# zhuzhuan1.net
KiCad netlist of a schematic drawn in Altium Designer
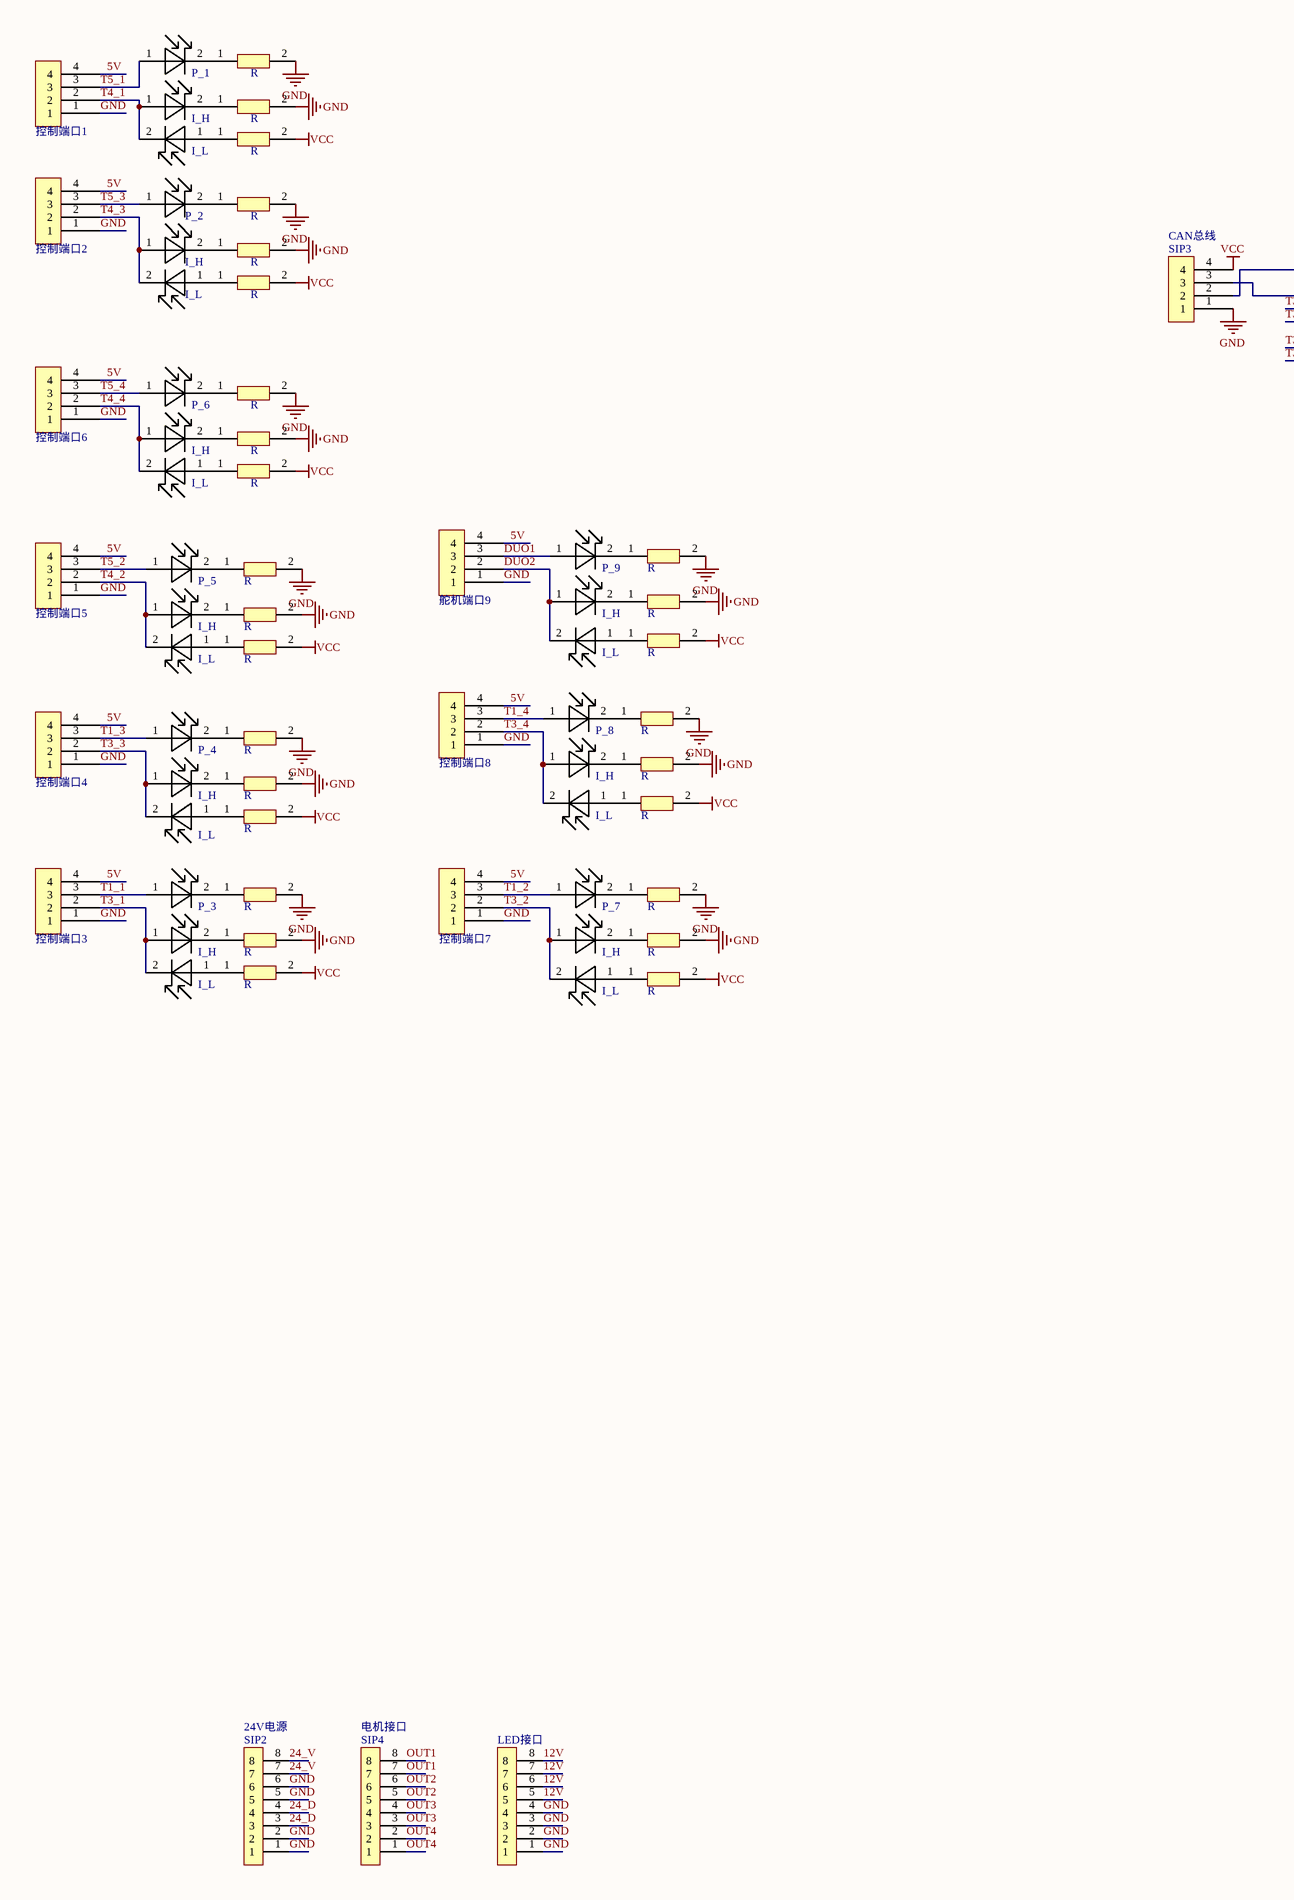
[diagram p0: zhuzhuan1.SchDoc, left]
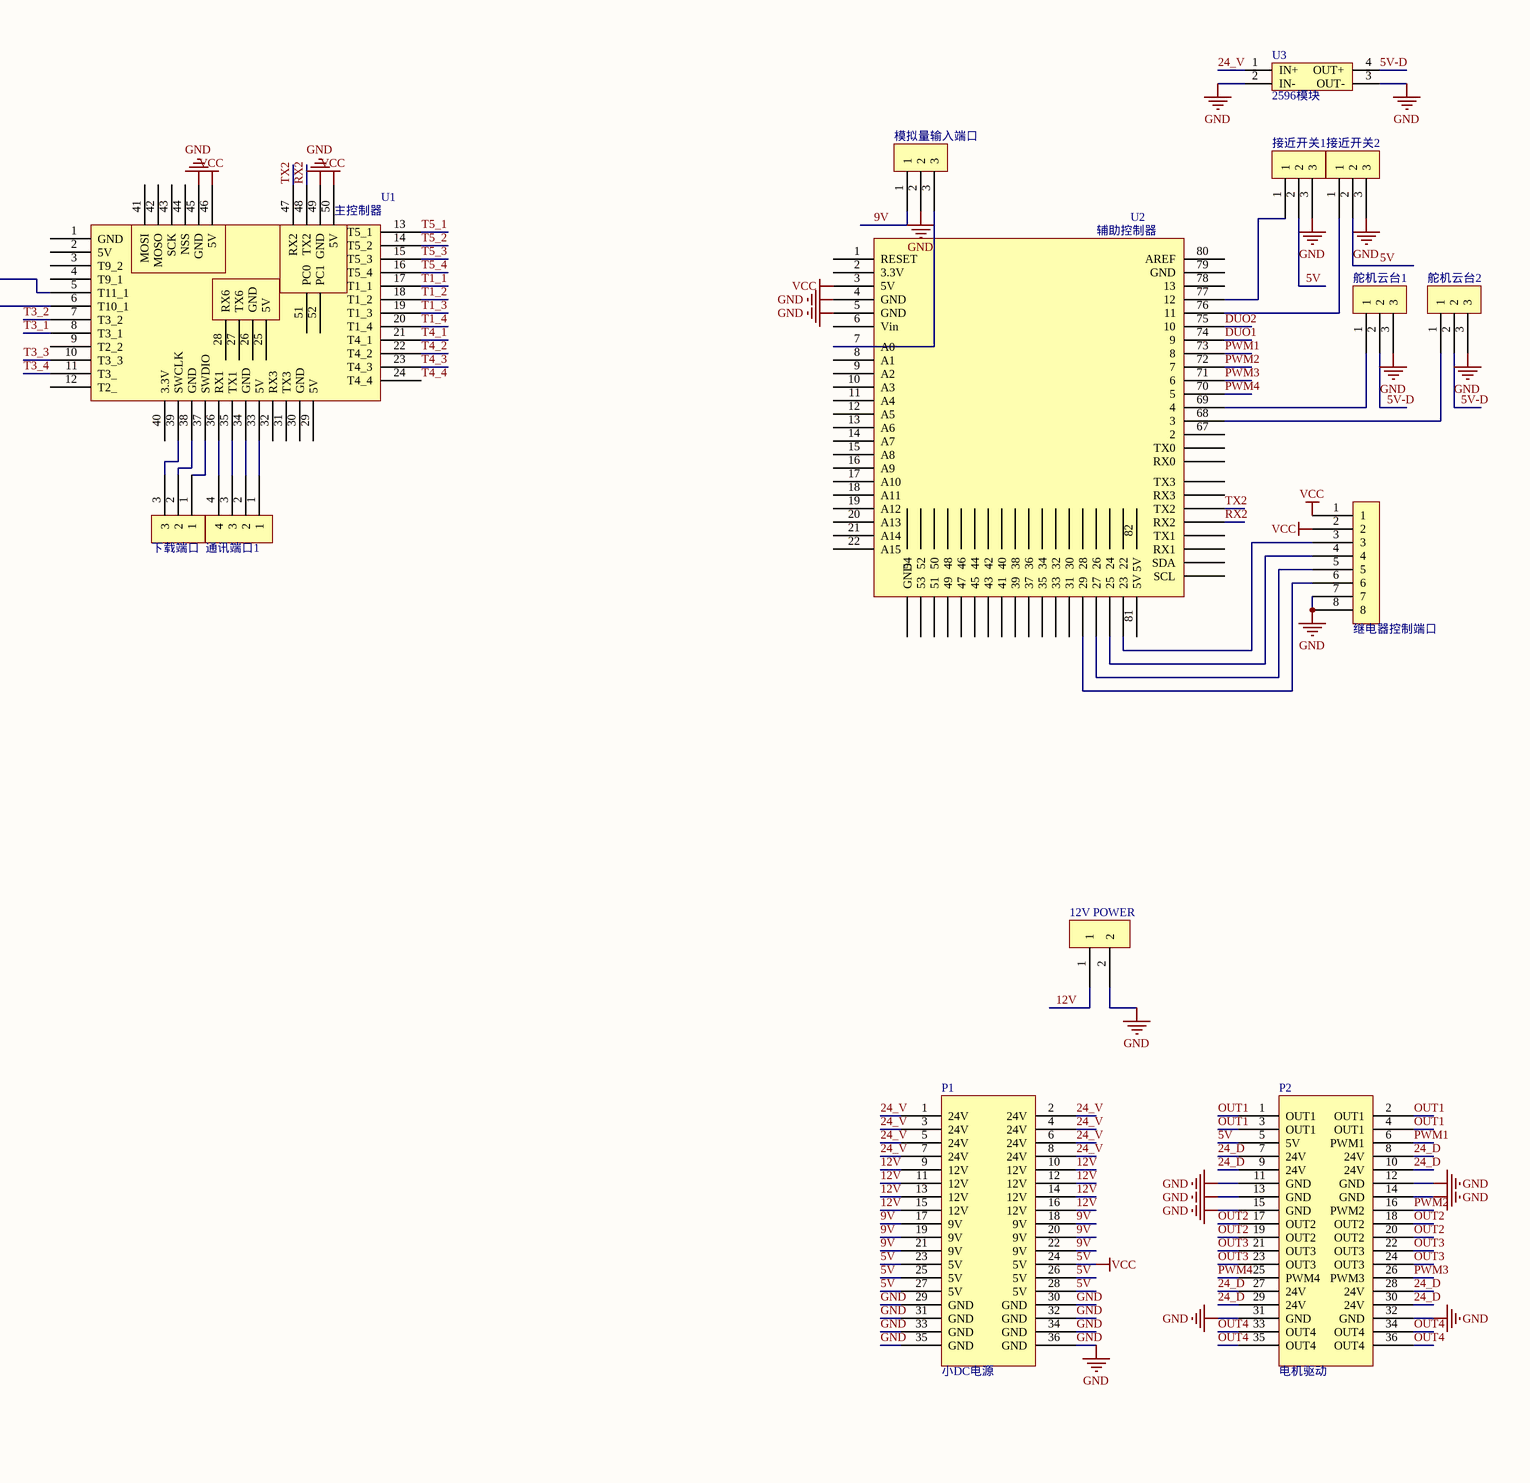
[diagram p1: zhuzhuan1.SchDoc, right]

(export (version "E")
  (design (tool "Eeschema 10.0.6"))
  (components
    (comp (ref "12V POWER") (value "SIP2") (footprint "SIP2-3MM") (libsource (lib "qudong") (part "SIP2")))
    (comp (ref "L1") (value "P_1") (footprint "LED-T") (libsource (lib "qudong") (part "LED")))
    (comp (ref "L2") (value "I_H") (footprint "LED-T") (libsource (lib "qudong") (part "LED")))
    (comp (ref "L3") (value "I_L") (footprint "LED-T") (libsource (lib "qudong") (part "LED")))
    (comp (ref "L4") (value "P_2") (footprint "LED-T") (libsource (lib "qudong") (part "LED")))
    (comp (ref "L5") (value "I_H") (footprint "LED-T") (libsource (lib "qudong") (part "LED")))
    (comp (ref "L6") (value "I_L") (footprint "LED-T") (libsource (lib "qudong") (part "LED")))
    (comp (ref "L7") (value "P_3") (footprint "LED-T") (libsource (lib "qudong") (part "LED")))
    (comp (ref "L8") (value "I_H") (footprint "LED-T") (libsource (lib "qudong") (part "LED")))
    (comp (ref "L9") (value "I_L") (footprint "LED-T") (libsource (lib "qudong") (part "LED")))
    (comp (ref "L10") (value "P_4") (footprint "LED-T") (libsource (lib "qudong") (part "LED")))
    (comp (ref "L11") (value "I_H") (footprint "LED-T") (libsource (lib "qudong") (part "LED")))
    (comp (ref "L12") (value "I_L") (footprint "LED-T") (libsource (lib "qudong") (part "LED")))
    (comp (ref "L13") (value "P_5") (footprint "LED-T") (libsource (lib "qudong") (part "LED")))
    (comp (ref "L14") (value "I_H") (footprint "LED-T") (libsource (lib "qudong") (part "LED")))
    (comp (ref "L15") (value "I_L") (footprint "LED-T") (libsource (lib "qudong") (part "LED")))
    (comp (ref "L16") (value "P_6") (footprint "LED-T") (libsource (lib "qudong") (part "LED")))
    (comp (ref "L17") (value "I_H") (footprint "LED-T") (libsource (lib "qudong") (part "LED")))
    (comp (ref "L18") (value "I_L") (footprint "LED-T") (libsource (lib "qudong") (part "LED")))
    (comp (ref "L19") (value "P_7") (footprint "LED-T") (libsource (lib "qudong") (part "LED")))
    (comp (ref "L20") (value "I_H") (footprint "LED-T") (libsource (lib "qudong") (part "LED")))
    (comp (ref "L21") (value "I_L") (footprint "LED-T") (libsource (lib "qudong") (part "LED")))
    (comp (ref "L22") (value "P_8") (footprint "LED-T") (libsource (lib "qudong") (part "LED")))
    (comp (ref "L23") (value "I_H") (footprint "LED-T") (libsource (lib "qudong") (part "LED")))
    (comp (ref "L24") (value "I_L") (footprint "LED-T") (libsource (lib "qudong") (part "LED")))
    (comp (ref "L25") (value "P_9") (footprint "LED-T") (libsource (lib "qudong") (part "LED")))
    (comp (ref "L26") (value "I_H") (footprint "LED-T") (libsource (lib "qudong") (part "LED")))
    (comp (ref "L27") (value "I_L") (footprint "LED-T") (libsource (lib "qudong") (part "LED")))
    (comp (ref "P1")
      (value "小DC电源")
      (footprint "DIP36-3.96MM")
      (libsource (lib "qudong") (part "POWER_18*2"))
    )
    (comp (ref "P2") (value "电机驱动") (footprint "DIP36-3.96MM") (libsource (lib "qudong") (part "Header")))
    (comp (ref "R1") (value "R") (footprint "RES-T") (libsource (lib "qudong") (part "RES-T")))
    (comp (ref "R2") (value "R") (footprint "RES-T") (libsource (lib "qudong") (part "RES-T")))
    (comp (ref "R3") (value "R") (footprint "RES-T") (libsource (lib "qudong") (part "RES-T")))
    (comp (ref "R4") (value "R") (footprint "RES-T") (libsource (lib "qudong") (part "RES-T")))
    (comp (ref "R5") (value "R") (footprint "RES-T") (libsource (lib "qudong") (part "RES-T")))
    (comp (ref "R6") (value "R") (footprint "RES-T") (libsource (lib "qudong") (part "RES-T")))
    (comp (ref "R7") (value "R") (footprint "RES-T") (libsource (lib "qudong") (part "RES-T")))
    (comp (ref "R8") (value "R") (footprint "RES-T") (libsource (lib "qudong") (part "RES-T")))
    (comp (ref "R9") (value "R") (footprint "RES-T") (libsource (lib "qudong") (part "RES-T")))
    (comp (ref "R10") (value "R") (footprint "RES-T") (libsource (lib "qudong") (part "RES-T")))
    (comp (ref "R11") (value "R") (footprint "RES-T") (libsource (lib "qudong") (part "RES-T")))
    (comp (ref "R12") (value "R") (footprint "RES-T") (libsource (lib "qudong") (part "RES-T")))
    (comp (ref "R13") (value "R") (footprint "RES-T") (libsource (lib "qudong") (part "RES-T")))
    (comp (ref "R14") (value "R") (footprint "RES-T") (libsource (lib "qudong") (part "RES-T")))
    (comp (ref "R15") (value "R") (footprint "RES-T") (libsource (lib "qudong") (part "RES-T")))
    (comp (ref "R16") (value "R") (footprint "RES-T") (libsource (lib "qudong") (part "RES-T")))
    (comp (ref "R17") (value "R") (footprint "RES-T") (libsource (lib "qudong") (part "RES-T")))
    (comp (ref "R18") (value "R") (footprint "RES-T") (libsource (lib "qudong") (part "RES-T")))
    (comp (ref "R19") (value "R") (footprint "RES-T") (libsource (lib "qudong") (part "RES-T")))
    (comp (ref "R20") (value "R") (footprint "RES-T") (libsource (lib "qudong") (part "RES-T")))
    (comp (ref "R21") (value "R") (footprint "RES-T") (libsource (lib "qudong") (part "RES-T")))
    (comp (ref "R22") (value "R") (footprint "RES-T") (libsource (lib "qudong") (part "RES-T")))
    (comp (ref "R23") (value "R") (footprint "RES-T") (libsource (lib "qudong") (part "RES-T")))
    (comp (ref "R24") (value "R") (footprint "RES-T") (libsource (lib "qudong") (part "RES-T")))
    (comp (ref "R25") (value "R") (footprint "RES-T") (libsource (lib "qudong") (part "RES-T")))
    (comp (ref "R26") (value "R") (footprint "RES-T") (libsource (lib "qudong") (part "RES-T")))
    (comp (ref "R27") (value "R") (footprint "RES-T") (libsource (lib "qudong") (part "RES-T")))
    (comp (ref "SIP2") (value "24V电源") (footprint "SIP8*3MM") (libsource (lib "qudong") (part "SIP8*3MM")))
    (comp (ref "SIP3") (value "CAN总线") (footprint "SIP4") (libsource (lib "qudong") (part "SIP4")))
    (comp (ref "SIP4") (value "电机接口") (footprint "SIP8*3MM") (libsource (lib "qudong") (part "SIP8*3MM")))
    (comp (ref "SIP5") (value "下载端口") (footprint "SIP3") (libsource (lib "") (part "SIP3_1")))
    (comp (ref "SIP7") (value "控制端口1") (footprint "SIP4") (libsource (lib "qudong") (part "SIP4")))
    (comp (ref "SIP8") (value "控制端口2") (footprint "SIP4") (libsource (lib "qudong") (part "SIP4")))
    (comp (ref "SIP9") (value "控制端口3") (footprint "SIP4") (libsource (lib "qudong") (part "SIP4")))
    (comp (ref "SIP10") (value "控制端口4") (footprint "SIP4") (libsource (lib "qudong") (part "SIP4")))
    (comp (ref "SIP11") (value "控制端口5") (footprint "SIP4") (libsource (lib "qudong") (part "SIP4")))
    (comp (ref "SIP12") (value "控制端口6") (footprint "SIP4") (libsource (lib "qudong") (part "SIP4")))
    (comp (ref "SIP13") (value "控制端口7") (footprint "SIP4") (libsource (lib "qudong") (part "SIP4")))
    (comp (ref "SIP14") (value "控制端口8") (footprint "SIP4") (libsource (lib "qudong") (part "SIP4")))
    (comp (ref "SIP15") (value "舵机云台1") (footprint "SIP3-3MM") (libsource (lib "qudong") (part "SIP3")))
    (comp (ref "SIP16") (value "舵机云台2") (footprint "SIP3-3MM") (libsource (lib "qudong") (part "SIP3")))
    (comp (ref "SIP17") (value "模拟量输入端口") (footprint "SIP3-3MM") (libsource (lib "qudong") (part "SIP3")))
    (comp (ref "SIP18") (value "舵机端口9") (footprint "SIP4") (libsource (lib "qudong") (part "SIP4")))
    (comp (ref "SIP19") (value "LED接口") (footprint "SIP8*3MM") (libsource (lib "qudong") (part "SIP8*3MM")))
    (comp (ref "SIP20") (value "接近开关1") (footprint "SIP3-3MM") (libsource (lib "qudong") (part "SIP3")))
    (comp (ref "SIP21") (value "接近开关2") (footprint "SIP3-3MM") (libsource (lib "qudong") (part "SIP3")))
    (comp (ref "SIP22") (value "继电器控制端口") (footprint "SIP8") (libsource (lib "qudong") (part "SIP8")))
    (comp (ref "U1")
      (value "主控制器")
      (footprint "-----STM32F407-----")
      (libsource (lib "qudong") (part "------STM32F407------"))
    )
    (comp (ref "U2")
      (value "辅助控制器")
      (footprint "ARDUINO 2560")
      (libsource (lib "qudong") (part "ARDUINO 2560"))
    )
    (comp (ref "U3") (value "2596模块") (footprint "2596模块") (libsource (lib "qudong") (part "2596模块")))
    (comp (ref "通讯端口1") (value "SIP4") (footprint "SIP4") (libsource (lib "") (part "SIP4_1")))
  )
  (nets
    (net (code "1") (name "/5V-D") (class "Default")
      (node (ref "SIP15") (pin "2") (pinfunction "2_2") (pintype "passive"))
      (node (ref "SIP16") (pin "2") (pinfunction "2_2") (pintype "passive"))
      (node (ref "U3") (pin "4") (pinfunction "OUT+_4") (pintype "passive"))
    )
    (net (code "2") (name "/9V") (class "Default")
      (node (ref "P1") (pin "17") (pinfunction "9V_17") (pintype "passive"))
      (node (ref "P1") (pin "18") (pinfunction "9V_18") (pintype "passive"))
      (node (ref "P1") (pin "19") (pinfunction "9V_19") (pintype "passive"))
      (node (ref "P1") (pin "20") (pinfunction "9V_20") (pintype "passive"))
      (node (ref "P1") (pin "21") (pinfunction "9V_21") (pintype "passive"))
      (node (ref "P1") (pin "22") (pinfunction "9V_22") (pintype "passive"))
      (node (ref "SIP17") (pin "1") (pinfunction "1_1") (pintype "passive"))
    )
    (net (code "3") (name "/12V") (class "Default")
      (node (ref "12V POWER") (pin "1") (pinfunction "1_1") (pintype "passive"))
      (node (ref "P1") (pin "10") (pinfunction "12V_10") (pintype "passive"))
      (node (ref "P1") (pin "11") (pinfunction "12V_11") (pintype "passive"))
      (node (ref "P1") (pin "12") (pinfunction "12V_12") (pintype "passive"))
      (node (ref "P1") (pin "13") (pinfunction "12V_13") (pintype "passive"))
      (node (ref "P1") (pin "14") (pinfunction "12V_14") (pintype "passive"))
      (node (ref "P1") (pin "15") (pinfunction "12V_15") (pintype "passive"))
      (node (ref "P1") (pin "16") (pinfunction "12V_16") (pintype "passive"))
      (node (ref "P1") (pin "9") (pinfunction "12V_9") (pintype "passive"))
      (node (ref "SIP19") (pin "5") (pinfunction "5_5") (pintype "passive"))
      (node (ref "SIP19") (pin "6") (pinfunction "6_6") (pintype "passive"))
      (node (ref "SIP19") (pin "7") (pinfunction "7_7") (pintype "passive"))
      (node (ref "SIP19") (pin "8") (pinfunction "8_8") (pintype "passive"))
    )
    (net (code "4") (name "/24_D") (class "Default")
      (node (ref "P2") (pin "10") (pinfunction "24V_10") (pintype "passive"))
      (node (ref "P2") (pin "27") (pinfunction "24V_27") (pintype "passive"))
      (node (ref "P2") (pin "28") (pinfunction "24V_28") (pintype "passive"))
      (node (ref "P2") (pin "29") (pinfunction "24V_29") (pintype "passive"))
      (node (ref "P2") (pin "30") (pinfunction "24V_30") (pintype "passive"))
      (node (ref "P2") (pin "7") (pinfunction "24V_7") (pintype "passive"))
      (node (ref "P2") (pin "8") (pinfunction "24V_8") (pintype "passive"))
      (node (ref "P2") (pin "9") (pinfunction "24V_9") (pintype "passive"))
      (node (ref "SIP2") (pin "3") (pinfunction "3_3") (pintype "passive"))
      (node (ref "SIP2") (pin "4") (pinfunction "4_4") (pintype "passive"))
    )
    (net (code "5") (name "/24_V") (class "Default")
      (node (ref "P1") (pin "1") (pinfunction "24V_1") (pintype "passive"))
      (node (ref "P1") (pin "2") (pinfunction "24V_2") (pintype "passive"))
      (node (ref "P1") (pin "3") (pinfunction "24V_3") (pintype "passive"))
      (node (ref "P1") (pin "4") (pinfunction "24V_4") (pintype "passive"))
      (node (ref "P1") (pin "5") (pinfunction "24V_5") (pintype "passive"))
      (node (ref "P1") (pin "6") (pinfunction "24V_6") (pintype "passive"))
      (node (ref "P1") (pin "7") (pinfunction "24V_7") (pintype "passive"))
      (node (ref "P1") (pin "8") (pinfunction "24V_8") (pintype "passive"))
      (node (ref "SIP2") (pin "7") (pinfunction "7_7") (pintype "passive"))
      (node (ref "SIP2") (pin "8") (pinfunction "8_8") (pintype "passive"))
      (node (ref "U3") (pin "1") (pinfunction "IN+_1") (pintype "passive"))
    )
    (net (code "6") (name "/DUO1") (class "Default")
      (node (ref "L25") (pin "1") (pinfunction "1_1") (pintype "passive"))
      (node (ref "SIP18") (pin "3") (pinfunction "3_3") (pintype "passive"))
      (node (ref "U2") (pin "74") (pinfunction "9_74") (pintype "passive"))
    )
    (net (code "7") (name "/DUO2") (class "Default")
      (node (ref "L26") (pin "1") (pinfunction "1_1") (pintype "passive"))
      (node (ref "L27") (pin "2") (pinfunction "2_2") (pintype "passive"))
      (node (ref "SIP18") (pin "2") (pinfunction "2_2") (pintype "passive"))
      (node (ref "U2") (pin "75") (pinfunction "10_75") (pintype "passive"))
    )
    (net (code "8") (name "/OUT1") (class "Default")
      (node (ref "P2") (pin "1") (pinfunction "OUT1_1") (pintype "passive"))
      (node (ref "P2") (pin "2") (pinfunction "OUT1_2") (pintype "passive"))
      (node (ref "P2") (pin "3") (pinfunction "OUT1_3") (pintype "passive"))
      (node (ref "P2") (pin "4") (pinfunction "OUT1_4") (pintype "passive"))
      (node (ref "SIP4") (pin "7") (pinfunction "7_7") (pintype "passive"))
      (node (ref "SIP4") (pin "8") (pinfunction "8_8") (pintype "passive"))
    )
    (net (code "9") (name "/OUT2") (class "Default")
      (node (ref "P2") (pin "17") (pinfunction "OUT2_17") (pintype "passive"))
      (node (ref "P2") (pin "18") (pinfunction "OUT2_18") (pintype "passive"))
      (node (ref "P2") (pin "19") (pinfunction "OUT2_19") (pintype "passive"))
      (node (ref "P2") (pin "20") (pinfunction "OUT2_20") (pintype "passive"))
      (node (ref "SIP4") (pin "5") (pinfunction "5_5") (pintype "passive"))
      (node (ref "SIP4") (pin "6") (pinfunction "6_6") (pintype "passive"))
    )
    (net (code "10") (name "/OUT3") (class "Default")
      (node (ref "P2") (pin "21") (pinfunction "OUT3_21") (pintype "passive"))
      (node (ref "P2") (pin "22") (pinfunction "OUT3_22") (pintype "passive"))
      (node (ref "P2") (pin "23") (pinfunction "OUT3_23") (pintype "passive"))
      (node (ref "P2") (pin "24") (pinfunction "OUT3_24") (pintype "passive"))
      (node (ref "SIP4") (pin "3") (pinfunction "3_3") (pintype "passive"))
      (node (ref "SIP4") (pin "4") (pinfunction "4_4") (pintype "passive"))
    )
    (net (code "11") (name "/OUT4") (class "Default")
      (node (ref "P2") (pin "33") (pinfunction "OUT4_33") (pintype "passive"))
      (node (ref "P2") (pin "34") (pinfunction "OUT4_34") (pintype "passive"))
      (node (ref "P2") (pin "35") (pinfunction "OUT4_35") (pintype "passive"))
      (node (ref "P2") (pin "36") (pinfunction "OUT4_36") (pintype "passive"))
      (node (ref "SIP4") (pin "1") (pinfunction "1_1") (pintype "passive"))
      (node (ref "SIP4") (pin "2") (pinfunction "2_2") (pintype "passive"))
    )
    (net (code "12") (name "/PWM1") (class "Default")
      (node (ref "P2") (pin "6") (pinfunction "PWM1_6") (pintype "passive"))
      (node (ref "U2") (pin "73") (pinfunction "8_73") (pintype "passive"))
    )
    (net (code "13") (name "/PWM2") (class "Default")
      (node (ref "P2") (pin "16") (pinfunction "PWM2_16") (pintype "passive"))
      (node (ref "U2") (pin "72") (pinfunction "7_72") (pintype "passive"))
    )
    (net (code "14") (name "/PWM3") (class "Default")
      (node (ref "P2") (pin "26") (pinfunction "PWM3_26") (pintype "passive"))
      (node (ref "U2") (pin "71") (pinfunction "6_71") (pintype "passive"))
    )
    (net (code "15") (name "/PWM4") (class "Default")
      (node (ref "P2") (pin "25") (pinfunction "PWM4_25") (pintype "passive"))
      (node (ref "U2") (pin "70") (pinfunction "5_70") (pintype "passive"))
    )
    (net (code "16") (name "/RX2") (class "Default")
      (node (ref "U1") (pin "48") (pinfunction "TX2_48") (pintype "passive"))
      (node (ref "U2") (pin "61") (pinfunction "RX2_61") (pintype "passive"))
    )
    (net (code "17") (name "/T1_1") (class "Default")
      (node (ref "L7") (pin "1") (pinfunction "1_1") (pintype "passive"))
      (node (ref "SIP9") (pin "3") (pinfunction "3_3") (pintype "passive"))
      (node (ref "U1") (pin "17") (pinfunction "T1_1_17") (pintype "passive"))
    )
    (net (code "18") (name "/T1_2") (class "Default")
      (node (ref "L19") (pin "1") (pinfunction "1_1") (pintype "passive"))
      (node (ref "SIP13") (pin "3") (pinfunction "3_3") (pintype "passive"))
      (node (ref "U1") (pin "18") (pinfunction "T1_2_18") (pintype "passive"))
    )
    (net (code "19") (name "/T1_3") (class "Default")
      (node (ref "L10") (pin "1") (pinfunction "1_1") (pintype "passive"))
      (node (ref "SIP10") (pin "3") (pinfunction "3_3") (pintype "passive"))
      (node (ref "U1") (pin "19") (pinfunction "T1_3_19") (pintype "passive"))
    )
    (net (code "20") (name "/T1_4") (class "Default")
      (node (ref "L22") (pin "1") (pinfunction "1_1") (pintype "passive"))
      (node (ref "SIP14") (pin "3") (pinfunction "3_3") (pintype "passive"))
      (node (ref "U1") (pin "20") (pinfunction "T1_4_20") (pintype "passive"))
    )
    (net (code "21") (name "/T3_1") (class "Default")
      (node (ref "L8") (pin "1") (pinfunction "1_1") (pintype "passive"))
      (node (ref "L9") (pin "2") (pinfunction "2_2") (pintype "passive"))
      (node (ref "SIP9") (pin "2") (pinfunction "2_2") (pintype "passive"))
      (node (ref "U1") (pin "8") (pinfunction "T3_1_8") (pintype "passive"))
    )
    (net (code "22") (name "/T3_2") (class "Default")
      (node (ref "L20") (pin "1") (pinfunction "1_1") (pintype "passive"))
      (node (ref "L21") (pin "2") (pinfunction "2_2") (pintype "passive"))
      (node (ref "SIP13") (pin "2") (pinfunction "2_2") (pintype "passive"))
      (node (ref "U1") (pin "7") (pinfunction "T3_2_7") (pintype "passive"))
    )
    (net (code "23") (name "/T3_3") (class "Default")
      (node (ref "L11") (pin "1") (pinfunction "1_1") (pintype "passive"))
      (node (ref "L12") (pin "2") (pinfunction "2_2") (pintype "passive"))
      (node (ref "SIP10") (pin "2") (pinfunction "2_2") (pintype "passive"))
      (node (ref "U1") (pin "10") (pinfunction "T3_3_10") (pintype "passive"))
    )
    (net (code "24") (name "/T3_4") (class "Default")
      (node (ref "L23") (pin "1") (pinfunction "1_1") (pintype "passive"))
      (node (ref "L24") (pin "2") (pinfunction "2_2") (pintype "passive"))
      (node (ref "SIP14") (pin "2") (pinfunction "2_2") (pintype "passive"))
      (node (ref "U1") (pin "11") (pinfunction "T3__11") (pintype "passive"))
    )
    (net (code "25") (name "/T4_1") (class "Default")
      (node (ref "L2") (pin "1") (pinfunction "1_1") (pintype "passive"))
      (node (ref "L3") (pin "2") (pinfunction "2_2") (pintype "passive"))
      (node (ref "SIP7") (pin "2") (pinfunction "2_2") (pintype "passive"))
      (node (ref "U1") (pin "21") (pinfunction "T4_1_21") (pintype "passive"))
    )
    (net (code "26") (name "/T4_2") (class "Default")
      (node (ref "L14") (pin "1") (pinfunction "1_1") (pintype "passive"))
      (node (ref "L15") (pin "2") (pinfunction "2_2") (pintype "passive"))
      (node (ref "SIP11") (pin "2") (pinfunction "2_2") (pintype "passive"))
      (node (ref "U1") (pin "22") (pinfunction "T4_2_22") (pintype "passive"))
    )
    (net (code "27") (name "/T4_3") (class "Default")
      (node (ref "L5") (pin "1") (pinfunction "1_1") (pintype "passive"))
      (node (ref "L6") (pin "2") (pinfunction "2_2") (pintype "passive"))
      (node (ref "SIP8") (pin "2") (pinfunction "2_2") (pintype "passive"))
      (node (ref "U1") (pin "23") (pinfunction "T4_3_23") (pintype "passive"))
    )
    (net (code "28") (name "/T4_4") (class "Default")
      (node (ref "L17") (pin "1") (pinfunction "1_1") (pintype "passive"))
      (node (ref "L18") (pin "2") (pinfunction "2_2") (pintype "passive"))
      (node (ref "SIP12") (pin "2") (pinfunction "2_2") (pintype "passive"))
      (node (ref "U1") (pin "24") (pinfunction "T4_4_24") (pintype "passive"))
    )
    (net (code "29") (name "/T5_1") (class "Default")
      (node (ref "L1") (pin "1") (pinfunction "1_1") (pintype "passive"))
      (node (ref "SIP7") (pin "3") (pinfunction "3_3") (pintype "passive"))
      (node (ref "U1") (pin "13") (pinfunction "T5_1_13") (pintype "passive"))
    )
    (net (code "30") (name "/T5_2") (class "Default")
      (node (ref "L13") (pin "1") (pinfunction "1_1") (pintype "passive"))
      (node (ref "SIP11") (pin "3") (pinfunction "3_3") (pintype "passive"))
      (node (ref "U1") (pin "14") (pinfunction "T5_2_14") (pintype "passive"))
    )
    (net (code "31") (name "/T5_3") (class "Default")
      (node (ref "L4") (pin "1") (pinfunction "1_1") (pintype "passive"))
      (node (ref "SIP8") (pin "3") (pinfunction "3_3") (pintype "passive"))
      (node (ref "U1") (pin "15") (pinfunction "T5_3_15") (pintype "passive"))
    )
    (net (code "32") (name "/T5_4") (class "Default")
      (node (ref "L16") (pin "1") (pinfunction "1_1") (pintype "passive"))
      (node (ref "SIP12") (pin "3") (pinfunction "3_3") (pintype "passive"))
      (node (ref "U1") (pin "16") (pinfunction "T5_4_16") (pintype "passive"))
    )
    (net (code "33") (name "/TX2") (class "Default")
      (node (ref "U1") (pin "47") (pinfunction "RX2_47") (pintype "passive"))
      (node (ref "U2") (pin "62") (pinfunction "TX2_62") (pintype "passive"))
    )
    (net (code "34") (name "GND") (class "Default")
      (node (ref "12V POWER") (pin "2") (pinfunction "2_2") (pintype "passive"))
      (node (ref "P1") (pin "29") (pinfunction "GND_29") (pintype "passive"))
      (node (ref "P1") (pin "30") (pinfunction "GND_30") (pintype "passive"))
      (node (ref "P1") (pin "31") (pinfunction "GND_31") (pintype "passive"))
      (node (ref "P1") (pin "32") (pinfunction "GND_32") (pintype "passive"))
      (node (ref "P1") (pin "33") (pinfunction "GND_33") (pintype "passive"))
      (node (ref "P1") (pin "34") (pinfunction "GND_34") (pintype "passive"))
      (node (ref "P1") (pin "35") (pinfunction "GND_35") (pintype "passive"))
      (node (ref "P1") (pin "36") (pinfunction "GND_36") (pintype "passive"))
      (node (ref "P2") (pin "11") (pinfunction "GND_11") (pintype "passive"))
      (node (ref "P2") (pin "12") (pinfunction "GND_12") (pintype "passive"))
      (node (ref "P2") (pin "13") (pinfunction "GND_13") (pintype "passive"))
      (node (ref "P2") (pin "14") (pinfunction "GND_14") (pintype "passive"))
      (node (ref "P2") (pin "15") (pinfunction "GND_15") (pintype "passive"))
      (node (ref "P2") (pin "31") (pinfunction "GND_31") (pintype "passive"))
      (node (ref "P2") (pin "32") (pinfunction "GND_32") (pintype "passive"))
      (node (ref "R1") (pin "2") (pinfunction "2_2") (pintype "passive"))
      (node (ref "R10") (pin "2") (pinfunction "2_2") (pintype "passive"))
      (node (ref "R11") (pin "2") (pinfunction "2_2") (pintype "passive"))
      (node (ref "R13") (pin "2") (pinfunction "2_2") (pintype "passive"))
      (node (ref "R14") (pin "2") (pinfunction "2_2") (pintype "passive"))
      (node (ref "R16") (pin "2") (pinfunction "2_2") (pintype "passive"))
      (node (ref "R17") (pin "2") (pinfunction "2_2") (pintype "passive"))
      (node (ref "R19") (pin "2") (pinfunction "2_2") (pintype "passive"))
      (node (ref "R2") (pin "2") (pinfunction "2_2") (pintype "passive"))
      (node (ref "R20") (pin "2") (pinfunction "2_2") (pintype "passive"))
      (node (ref "R22") (pin "2") (pinfunction "2_2") (pintype "passive"))
      (node (ref "R23") (pin "2") (pinfunction "2_2") (pintype "passive"))
      (node (ref "R25") (pin "2") (pinfunction "2_2") (pintype "passive"))
      (node (ref "R26") (pin "2") (pinfunction "2_2") (pintype "passive"))
      (node (ref "R4") (pin "2") (pinfunction "2_2") (pintype "passive"))
      (node (ref "R5") (pin "2") (pinfunction "2_2") (pintype "passive"))
      (node (ref "R7") (pin "2") (pinfunction "2_2") (pintype "passive"))
      (node (ref "R8") (pin "2") (pinfunction "2_2") (pintype "passive"))
      (node (ref "SIP10") (pin "1") (pinfunction "1_1") (pintype "passive"))
      (node (ref "SIP11") (pin "1") (pinfunction "1_1") (pintype "passive"))
      (node (ref "SIP12") (pin "1") (pinfunction "1_1") (pintype "passive"))
      (node (ref "SIP13") (pin "1") (pinfunction "1_1") (pintype "passive"))
      (node (ref "SIP14") (pin "1") (pinfunction "1_1") (pintype "passive"))
      (node (ref "SIP15") (pin "3") (pinfunction "3_3") (pintype "passive"))
      (node (ref "SIP16") (pin "3") (pinfunction "3_3") (pintype "passive"))
      (node (ref "SIP17") (pin "2") (pinfunction "2_2") (pintype "passive"))
      (node (ref "SIP18") (pin "1") (pinfunction "1_1") (pintype "passive"))
      (node (ref "SIP19") (pin "1") (pinfunction "1_1") (pintype "passive"))
      (node (ref "SIP19") (pin "2") (pinfunction "2_2") (pintype "passive"))
      (node (ref "SIP19") (pin "3") (pinfunction "3_3") (pintype "passive"))
      (node (ref "SIP19") (pin "4") (pinfunction "4_4") (pintype "passive"))
      (node (ref "SIP2") (pin "1") (pinfunction "1_1") (pintype "passive"))
      (node (ref "SIP2") (pin "2") (pinfunction "2_2") (pintype "passive"))
      (node (ref "SIP2") (pin "5") (pinfunction "5_5") (pintype "passive"))
      (node (ref "SIP2") (pin "6") (pinfunction "6_6") (pintype "passive"))
      (node (ref "SIP20") (pin "3") (pinfunction "3_3") (pintype "passive"))
      (node (ref "SIP21") (pin "3") (pinfunction "3_3") (pintype "passive"))
      (node (ref "SIP22") (pin "7") (pinfunction "7_7") (pintype "passive"))
      (node (ref "SIP22") (pin "8") (pinfunction "8_8") (pintype "passive"))
      (node (ref "SIP3") (pin "1") (pinfunction "1_1") (pintype "passive"))
      (node (ref "SIP7") (pin "1") (pinfunction "1_1") (pintype "passive"))
      (node (ref "SIP8") (pin "1") (pinfunction "1_1") (pintype "passive"))
      (node (ref "SIP9") (pin "1") (pinfunction "1_1") (pintype "passive"))
      (node (ref "U1") (pin "45") (pinfunction "GND_45") (pintype "passive"))
      (node (ref "U1") (pin "49") (pinfunction "GND_49") (pintype "passive"))
      (node (ref "U2") (pin "4") (pinfunction "GND_4") (pintype "passive"))
      (node (ref "U2") (pin "5") (pinfunction "GND_5") (pintype "passive"))
      (node (ref "U3") (pin "2") (pinfunction "IN-_2") (pintype "passive"))
      (node (ref "U3") (pin "3") (pinfunction "OUT-_3") (pintype "passive"))
    )
    (net (code "35") (name "Net-(L1-Pad2)") (class "Default")
      (node (ref "L1") (pin "2") (pinfunction "2_2") (pintype "passive"))
      (node (ref "R1") (pin "1") (pinfunction "1_1") (pintype "passive"))
    )
    (net (code "36") (name "Net-(L2-Pad2)") (class "Default")
      (node (ref "L2") (pin "2") (pinfunction "2_2") (pintype "passive"))
      (node (ref "R2") (pin "1") (pinfunction "1_1") (pintype "passive"))
    )
    (net (code "37") (name "Net-(L3-Pad1)") (class "Default")
      (node (ref "L3") (pin "1") (pinfunction "1_1") (pintype "passive"))
      (node (ref "R3") (pin "1") (pinfunction "1_1") (pintype "passive"))
    )
    (net (code "38") (name "Net-(L4-Pad2)") (class "Default")
      (node (ref "L4") (pin "2") (pinfunction "2_2") (pintype "passive"))
      (node (ref "R4") (pin "1") (pinfunction "1_1") (pintype "passive"))
    )
    (net (code "39") (name "Net-(L5-Pad2)") (class "Default")
      (node (ref "L5") (pin "2") (pinfunction "2_2") (pintype "passive"))
      (node (ref "R5") (pin "1") (pinfunction "1_1") (pintype "passive"))
    )
    (net (code "40") (name "Net-(L6-Pad1)") (class "Default")
      (node (ref "L6") (pin "1") (pinfunction "1_1") (pintype "passive"))
      (node (ref "R6") (pin "1") (pinfunction "1_1") (pintype "passive"))
    )
    (net (code "41") (name "Net-(L7-Pad2)") (class "Default")
      (node (ref "L7") (pin "2") (pinfunction "2_2") (pintype "passive"))
      (node (ref "R7") (pin "1") (pinfunction "1_1") (pintype "passive"))
    )
    (net (code "42") (name "Net-(L8-Pad2)") (class "Default")
      (node (ref "L8") (pin "2") (pinfunction "2_2") (pintype "passive"))
      (node (ref "R8") (pin "1") (pinfunction "1_1") (pintype "passive"))
    )
    (net (code "43") (name "Net-(L9-Pad1)") (class "Default")
      (node (ref "L9") (pin "1") (pinfunction "1_1") (pintype "passive"))
      (node (ref "R9") (pin "1") (pinfunction "1_1") (pintype "passive"))
    )
    (net (code "44") (name "Net-(L10-Pad2)") (class "Default")
      (node (ref "L10") (pin "2") (pinfunction "2_2") (pintype "passive"))
      (node (ref "R10") (pin "1") (pinfunction "1_1") (pintype "passive"))
    )
    (net (code "45") (name "Net-(L11-Pad2)") (class "Default")
      (node (ref "L11") (pin "2") (pinfunction "2_2") (pintype "passive"))
      (node (ref "R11") (pin "1") (pinfunction "1_1") (pintype "passive"))
    )
    (net (code "46") (name "Net-(L12-Pad1)") (class "Default")
      (node (ref "L12") (pin "1") (pinfunction "1_1") (pintype "passive"))
      (node (ref "R12") (pin "1") (pinfunction "1_1") (pintype "passive"))
    )
    (net (code "47") (name "Net-(L13-Pad2)") (class "Default")
      (node (ref "L13") (pin "2") (pinfunction "2_2") (pintype "passive"))
      (node (ref "R13") (pin "1") (pinfunction "1_1") (pintype "passive"))
    )
    (net (code "48") (name "Net-(L14-Pad2)") (class "Default")
      (node (ref "L14") (pin "2") (pinfunction "2_2") (pintype "passive"))
      (node (ref "R14") (pin "1") (pinfunction "1_1") (pintype "passive"))
    )
    (net (code "49") (name "Net-(L15-Pad1)") (class "Default")
      (node (ref "L15") (pin "1") (pinfunction "1_1") (pintype "passive"))
      (node (ref "R15") (pin "1") (pinfunction "1_1") (pintype "passive"))
    )
    (net (code "50") (name "Net-(L16-Pad2)") (class "Default")
      (node (ref "L16") (pin "2") (pinfunction "2_2") (pintype "passive"))
      (node (ref "R16") (pin "1") (pinfunction "1_1") (pintype "passive"))
    )
    (net (code "51") (name "Net-(L17-Pad2)") (class "Default")
      (node (ref "L17") (pin "2") (pinfunction "2_2") (pintype "passive"))
      (node (ref "R17") (pin "1") (pinfunction "1_1") (pintype "passive"))
    )
    (net (code "52") (name "Net-(L18-Pad1)") (class "Default")
      (node (ref "L18") (pin "1") (pinfunction "1_1") (pintype "passive"))
      (node (ref "R18") (pin "1") (pinfunction "1_1") (pintype "passive"))
    )
    (net (code "53") (name "Net-(L19-Pad2)") (class "Default")
      (node (ref "L19") (pin "2") (pinfunction "2_2") (pintype "passive"))
      (node (ref "R19") (pin "1") (pinfunction "1_1") (pintype "passive"))
    )
    (net (code "54") (name "Net-(L20-Pad2)") (class "Default")
      (node (ref "L20") (pin "2") (pinfunction "2_2") (pintype "passive"))
      (node (ref "R20") (pin "1") (pinfunction "1_1") (pintype "passive"))
    )
    (net (code "55") (name "Net-(L21-Pad1)") (class "Default")
      (node (ref "L21") (pin "1") (pinfunction "1_1") (pintype "passive"))
      (node (ref "R21") (pin "1") (pinfunction "1_1") (pintype "passive"))
    )
    (net (code "56") (name "Net-(L22-Pad2)") (class "Default")
      (node (ref "L22") (pin "2") (pinfunction "2_2") (pintype "passive"))
      (node (ref "R22") (pin "1") (pinfunction "1_1") (pintype "passive"))
    )
    (net (code "57") (name "Net-(L23-Pad2)") (class "Default")
      (node (ref "L23") (pin "2") (pinfunction "2_2") (pintype "passive"))
      (node (ref "R23") (pin "1") (pinfunction "1_1") (pintype "passive"))
    )
    (net (code "58") (name "Net-(L24-Pad1)") (class "Default")
      (node (ref "L24") (pin "1") (pinfunction "1_1") (pintype "passive"))
      (node (ref "R24") (pin "1") (pinfunction "1_1") (pintype "passive"))
    )
    (net (code "59") (name "Net-(L25-Pad2)") (class "Default")
      (node (ref "L25") (pin "2") (pinfunction "2_2") (pintype "passive"))
      (node (ref "R25") (pin "1") (pinfunction "1_1") (pintype "passive"))
    )
    (net (code "60") (name "Net-(L26-Pad2)") (class "Default")
      (node (ref "L26") (pin "2") (pinfunction "2_2") (pintype "passive"))
      (node (ref "R26") (pin "1") (pinfunction "1_1") (pintype "passive"))
    )
    (net (code "61") (name "Net-(L27-Pad1)") (class "Default")
      (node (ref "L27") (pin "1") (pinfunction "1_1") (pintype "passive"))
      (node (ref "R27") (pin "1") (pinfunction "1_1") (pintype "passive"))
    )
    (net (code "62") (name "Net-(SIP5-Pad2)") (class "Default")
      (node (ref "SIP5") (pin "2") (pinfunction "2_2") (pintype "passive"))
      (node (ref "U1") (pin "38") (pinfunction "GND_38") (pintype "passive"))
    )
    (net (code "63") (name "Net-(U1-5V-Pad33)") (class "Default")
      (node (ref "U1") (pin "33") (pinfunction "5V_33") (pintype "passive"))
      (node (ref "通讯端口1") (pin "1") (pinfunction "1_1") (pintype "passive"))
    )
    (net (code "64") (name "Net-(U1-GND-Pad34)") (class "Default")
      (node (ref "U1") (pin "34") (pinfunction "GND_34") (pintype "passive"))
      (node (ref "通讯端口1") (pin "2") (pinfunction "2_2") (pintype "passive"))
    )
    (net (code "65") (name "Net-(U1-RX1)") (class "Default")
      (node (ref "U1") (pin "36") (pinfunction "RX1_36") (pintype "passive"))
      (node (ref "通讯端口1") (pin "4") (pinfunction "4_4") (pintype "passive"))
    )
    (net (code "66") (name "Net-(U1-SWCLK)") (class "Default")
      (node (ref "SIP5") (pin "3") (pinfunction "3_3") (pintype "passive"))
      (node (ref "U1") (pin "39") (pinfunction "SWCLK_39") (pintype "passive"))
    )
    (net (code "67") (name "Net-(U1-SWDIO)") (class "Default")
      (node (ref "SIP5") (pin "1") (pinfunction "1_1") (pintype "passive"))
      (node (ref "U1") (pin "37") (pinfunction "SWDIO_37") (pintype "passive"))
    )
    (net (code "68") (name "Net-(U1-T10_1)") (class "Default")
      (node (ref "SIP3") (pin "3") (pinfunction "3_3") (pintype "passive"))
      (node (ref "U1") (pin "6") (pinfunction "T10_1_6") (pintype "passive"))
    )
    (net (code "69") (name "Net-(U1-T11_1)") (class "Default")
      (node (ref "SIP3") (pin "2") (pinfunction "2_2") (pintype "passive"))
      (node (ref "U1") (pin "5") (pinfunction "T11_1_5") (pintype "passive"))
    )
    (net (code "70") (name "Net-(U1-TX1)") (class "Default")
      (node (ref "U1") (pin "35") (pinfunction "TX1_35") (pintype "passive"))
      (node (ref "通讯端口1") (pin "3") (pinfunction "3_3") (pintype "passive"))
    )
    (net (code "71") (name "Net-(U2-3)") (class "Default")
      (node (ref "SIP16") (pin "1") (pinfunction "1_1") (pintype "passive"))
      (node (ref "U2") (pin "68") (pinfunction "3_68") (pintype "passive"))
    )
    (net (code "72") (name "Net-(U2-4)") (class "Default")
      (node (ref "SIP15") (pin "1") (pinfunction "1_1") (pintype "passive"))
      (node (ref "U2") (pin "69") (pinfunction "4_69") (pintype "passive"))
    )
    (net (code "73") (name "Net-(U2-11)") (class "Default")
      (node (ref "SIP21") (pin "1") (pinfunction "1_1") (pintype "passive"))
      (node (ref "U2") (pin "76") (pinfunction "11_76") (pintype "passive"))
    )
    (net (code "74") (name "Net-(U2-12)") (class "Default")
      (node (ref "SIP20") (pin "1") (pinfunction "1_1") (pintype "passive"))
      (node (ref "U2") (pin "77") (pinfunction "12_77") (pintype "passive"))
    )
    (net (code "75") (name "Net-(U2-23)") (class "Default")
      (node (ref "SIP22") (pin "3") (pinfunction "3_3") (pintype "passive"))
      (node (ref "U2") (pin "24") (pinfunction "23_24") (pintype "passive"))
    )
    (net (code "76") (name "Net-(U2-25)") (class "Default")
      (node (ref "SIP22") (pin "4") (pinfunction "4_4") (pintype "passive"))
      (node (ref "U2") (pin "26") (pinfunction "25_26") (pintype "passive"))
    )
    (net (code "77") (name "Net-(U2-27)") (class "Default")
      (node (ref "SIP22") (pin "5") (pinfunction "5_5") (pintype "passive"))
      (node (ref "U2") (pin "28") (pinfunction "27_28") (pintype "passive"))
    )
    (net (code "78") (name "Net-(U2-29)") (class "Default")
      (node (ref "SIP22") (pin "6") (pinfunction "6_6") (pintype "passive"))
      (node (ref "U2") (pin "30") (pinfunction "29_30") (pintype "passive"))
    )
    (net (code "79") (name "Net-(U2-A0)") (class "Default")
      (node (ref "SIP17") (pin "3") (pinfunction "3_3") (pintype "passive"))
      (node (ref "U2") (pin "7") (pinfunction "A0_7") (pintype "passive"))
    )
    (net (code "80") (name "VCC") (class "Default")
      (node (ref "P1") (pin "23") (pinfunction "5V_23") (pintype "passive"))
      (node (ref "P1") (pin "24") (pinfunction "5V_24") (pintype "passive"))
      (node (ref "P1") (pin "25") (pinfunction "5V_25") (pintype "passive"))
      (node (ref "P1") (pin "26") (pinfunction "5V_26") (pintype "passive"))
      (node (ref "P1") (pin "27") (pinfunction "5V_27") (pintype "passive"))
      (node (ref "P1") (pin "28") (pinfunction "5V_28") (pintype "passive"))
      (node (ref "P2") (pin "5") (pinfunction "5V_5") (pintype "passive"))
      (node (ref "R12") (pin "2") (pinfunction "2_2") (pintype "passive"))
      (node (ref "R15") (pin "2") (pinfunction "2_2") (pintype "passive"))
      (node (ref "R18") (pin "2") (pinfunction "2_2") (pintype "passive"))
      (node (ref "R21") (pin "2") (pinfunction "2_2") (pintype "passive"))
      (node (ref "R24") (pin "2") (pinfunction "2_2") (pintype "passive"))
      (node (ref "R27") (pin "2") (pinfunction "2_2") (pintype "passive"))
      (node (ref "R3") (pin "2") (pinfunction "2_2") (pintype "passive"))
      (node (ref "R6") (pin "2") (pinfunction "2_2") (pintype "passive"))
      (node (ref "R9") (pin "2") (pinfunction "2_2") (pintype "passive"))
      (node (ref "SIP10") (pin "4") (pinfunction "4_4") (pintype "passive"))
      (node (ref "SIP11") (pin "4") (pinfunction "4_4") (pintype "passive"))
      (node (ref "SIP12") (pin "4") (pinfunction "4_4") (pintype "passive"))
      (node (ref "SIP13") (pin "4") (pinfunction "4_4") (pintype "passive"))
      (node (ref "SIP14") (pin "4") (pinfunction "4_4") (pintype "passive"))
      (node (ref "SIP18") (pin "4") (pinfunction "4_4") (pintype "passive"))
      (node (ref "SIP20") (pin "2") (pinfunction "2_2") (pintype "passive"))
      (node (ref "SIP21") (pin "2") (pinfunction "2_2") (pintype "passive"))
      (node (ref "SIP22") (pin "1") (pinfunction "1_1") (pintype "passive"))
      (node (ref "SIP22") (pin "2") (pinfunction "2_2") (pintype "passive"))
      (node (ref "SIP3") (pin "4") (pinfunction "4_4") (pintype "passive"))
      (node (ref "SIP7") (pin "4") (pinfunction "4_4") (pintype "passive"))
      (node (ref "SIP8") (pin "4") (pinfunction "4_4") (pintype "passive"))
      (node (ref "SIP9") (pin "4") (pinfunction "4_4") (pintype "passive"))
      (node (ref "U1") (pin "46") (pinfunction "5V_46") (pintype "passive"))
      (node (ref "U1") (pin "50") (pinfunction "5V_50") (pintype "passive"))
      (node (ref "U2") (pin "3") (pinfunction "5V_3") (pintype "passive"))
    )
    (net (code "81") (name "unconnected-(U1-3.3V-Pad40)") (class "Default")
      (node (ref "U1") (pin "40") (pinfunction "3.3V_40") (pintype "passive"))
    )
    (net (code "82") (name "unconnected-(U1-5V-Pad2)") (class "Default")
      (node (ref "U1") (pin "2") (pinfunction "5V_2") (pintype "passive"))
    )
    (net (code "83") (name "unconnected-(U1-5V-Pad25)") (class "Default")
      (node (ref "U1") (pin "25") (pinfunction "5V_25") (pintype "passive"))
    )
    (net (code "84") (name "unconnected-(U1-5V-Pad29)") (class "Default")
      (node (ref "U1") (pin "29") (pinfunction "5V_29") (pintype "passive"))
    )
    (net (code "85") (name "unconnected-(U1-GND-Pad1)") (class "Default")
      (node (ref "U1") (pin "1") (pinfunction "GND_1") (pintype "passive"))
    )
    (net (code "86") (name "unconnected-(U1-GND-Pad26)") (class "Default")
      (node (ref "U1") (pin "26") (pinfunction "GND_26") (pintype "passive"))
    )
    (net (code "87") (name "unconnected-(U1-GND-Pad30)") (class "Default")
      (node (ref "U1") (pin "30") (pinfunction "GND_30") (pintype "passive"))
    )
    (net (code "88") (name "unconnected-(U1-MOSI-Pad41)") (class "Default")
      (node (ref "U1") (pin "41") (pinfunction "MOSI_41") (pintype "passive"))
    )
    (net (code "89") (name "unconnected-(U1-MOSO-Pad42)") (class "Default")
      (node (ref "U1") (pin "42") (pinfunction "MOSO_42") (pintype "passive"))
    )
    (net (code "90") (name "unconnected-(U1-NSS-Pad44)") (class "Default")
      (node (ref "U1") (pin "44") (pinfunction "NSS_44") (pintype "passive"))
    )
    (net (code "91") (name "unconnected-(U1-PC0-Pad51)") (class "Default")
      (node (ref "U1") (pin "51") (pinfunction "PC0_51") (pintype "passive"))
    )
    (net (code "92") (name "unconnected-(U1-PC1-Pad52)") (class "Default")
      (node (ref "U1") (pin "52") (pinfunction "PC1_52") (pintype "passive"))
    )
    (net (code "93") (name "unconnected-(U1-RX3-Pad32)") (class "Default")
      (node (ref "U1") (pin "32") (pinfunction "RX3_32") (pintype "passive"))
    )
    (net (code "94") (name "unconnected-(U1-RX6-Pad28)") (class "Default")
      (node (ref "U1") (pin "28") (pinfunction "RX6_28") (pintype "passive"))
    )
    (net (code "95") (name "unconnected-(U1-SCK-Pad43)") (class "Default")
      (node (ref "U1") (pin "43") (pinfunction "SCK_43") (pintype "passive"))
    )
    (net (code "96") (name "unconnected-(U1-T2_-Pad12)") (class "Default")
      (node (ref "U1") (pin "12") (pinfunction "T2__12") (pintype "passive"))
    )
    (net (code "97") (name "unconnected-(U1-T2_2-Pad9)") (class "Default")
      (node (ref "U1") (pin "9") (pinfunction "T2_2_9") (pintype "passive"))
    )
    (net (code "98") (name "unconnected-(U1-T9_1-Pad4)") (class "Default")
      (node (ref "U1") (pin "4") (pinfunction "T9_1_4") (pintype "passive"))
    )
    (net (code "99") (name "unconnected-(U1-T9_2-Pad3)") (class "Default")
      (node (ref "U1") (pin "3") (pinfunction "T9_2_3") (pintype "passive"))
    )
    (net (code "100") (name "unconnected-(U1-TX3-Pad31)") (class "Default")
      (node (ref "U1") (pin "31") (pinfunction "TX3_31") (pintype "passive"))
    )
    (net (code "101") (name "unconnected-(U1-TX6-Pad27)") (class "Default")
      (node (ref "U1") (pin "27") (pinfunction "TX6_27") (pintype "passive"))
    )
    (net (code "102") (name "unconnected-(U2-2-Pad67)") (class "Default")
      (node (ref "U2") (pin "67") (pinfunction "2_67") (pintype "passive"))
    )
    (net (code "103") (name "unconnected-(U2-3.3V-Pad2)") (class "Default")
      (node (ref "U2") (pin "2") (pinfunction "3.3V_2") (pintype "passive"))
    )
    (net (code "104") (name "unconnected-(U2-5V-Pad81)") (class "Default")
      (node (ref "U2") (pin "81") (pinfunction "5V_81") (pintype "passive"))
    )
    (net (code "105") (name "unconnected-(U2-5V-Pad82)") (class "Default")
      (node (ref "U2") (pin "82") (pinfunction "5V_82") (pintype "passive"))
    )
    (net (code "106") (name "unconnected-(U2-13-Pad78)") (class "Default")
      (node (ref "U2") (pin "78") (pinfunction "13_78") (pintype "passive"))
    )
    (net (code "107") (name "unconnected-(U2-22-Pad23)") (class "Default")
      (node (ref "U2") (pin "23") (pinfunction "22_23") (pintype "passive"))
    )
    (net (code "108") (name "unconnected-(U2-24-Pad25)") (class "Default")
      (node (ref "U2") (pin "25") (pinfunction "24_25") (pintype "passive"))
    )
    (net (code "109") (name "unconnected-(U2-26-Pad27)") (class "Default")
      (node (ref "U2") (pin "27") (pinfunction "26_27") (pintype "passive"))
    )
    (net (code "110") (name "unconnected-(U2-28-Pad29)") (class "Default")
      (node (ref "U2") (pin "29") (pinfunction "28_29") (pintype "passive"))
    )
    (net (code "111") (name "unconnected-(U2-30-Pad31)") (class "Default")
      (node (ref "U2") (pin "31") (pinfunction "30_31") (pintype "passive"))
    )
    (net (code "112") (name "unconnected-(U2-31-Pad32)") (class "Default")
      (node (ref "U2") (pin "32") (pinfunction "31_32") (pintype "passive"))
    )
    (net (code "113") (name "unconnected-(U2-32-Pad33)") (class "Default")
      (node (ref "U2") (pin "33") (pinfunction "32_33") (pintype "passive"))
    )
    (net (code "114") (name "unconnected-(U2-33-Pad34)") (class "Default")
      (node (ref "U2") (pin "34") (pinfunction "33_34") (pintype "passive"))
    )
    (net (code "115") (name "unconnected-(U2-34-Pad35)") (class "Default")
      (node (ref "U2") (pin "35") (pinfunction "34_35") (pintype "passive"))
    )
    (net (code "116") (name "unconnected-(U2-35-Pad36)") (class "Default")
      (node (ref "U2") (pin "36") (pinfunction "35_36") (pintype "passive"))
    )
    (net (code "117") (name "unconnected-(U2-36-Pad37)") (class "Default")
      (node (ref "U2") (pin "37") (pinfunction "36_37") (pintype "passive"))
    )
    (net (code "118") (name "unconnected-(U2-37-Pad38)") (class "Default")
      (node (ref "U2") (pin "38") (pinfunction "37_38") (pintype "passive"))
    )
    (net (code "119") (name "unconnected-(U2-38-Pad39)") (class "Default")
      (node (ref "U2") (pin "39") (pinfunction "38_39") (pintype "passive"))
    )
    (net (code "120") (name "unconnected-(U2-39-Pad40)") (class "Default")
      (node (ref "U2") (pin "40") (pinfunction "39_40") (pintype "passive"))
    )
    (net (code "121") (name "unconnected-(U2-40-Pad41)") (class "Default")
      (node (ref "U2") (pin "41") (pinfunction "40_41") (pintype "passive"))
    )
    (net (code "122") (name "unconnected-(U2-41-Pad42)") (class "Default")
      (node (ref "U2") (pin "42") (pinfunction "41_42") (pintype "passive"))
    )
    (net (code "123") (name "unconnected-(U2-42-Pad43)") (class "Default")
      (node (ref "U2") (pin "43") (pinfunction "42_43") (pintype "passive"))
    )
    (net (code "124") (name "unconnected-(U2-43-Pad44)") (class "Default")
      (node (ref "U2") (pin "44") (pinfunction "43_44") (pintype "passive"))
    )
    (net (code "125") (name "unconnected-(U2-44-Pad45)") (class "Default")
      (node (ref "U2") (pin "45") (pinfunction "44_45") (pintype "passive"))
    )
    (net (code "126") (name "unconnected-(U2-45-Pad46)") (class "Default")
      (node (ref "U2") (pin "46") (pinfunction "45_46") (pintype "passive"))
    )
    (net (code "127") (name "unconnected-(U2-46-Pad47)") (class "Default")
      (node (ref "U2") (pin "47") (pinfunction "46_47") (pintype "passive"))
    )
    (net (code "128") (name "unconnected-(U2-47-Pad48)") (class "Default")
      (node (ref "U2") (pin "48") (pinfunction "47_48") (pintype "passive"))
    )
    (net (code "129") (name "unconnected-(U2-48-Pad49)") (class "Default")
      (node (ref "U2") (pin "49") (pinfunction "48_49") (pintype "passive"))
    )
    (net (code "130") (name "unconnected-(U2-49-Pad50)") (class "Default")
      (node (ref "U2") (pin "50") (pinfunction "49_50") (pintype "passive"))
    )
    (net (code "131") (name "unconnected-(U2-50-Pad51)") (class "Default")
      (node (ref "U2") (pin "51") (pinfunction "50_51") (pintype "passive"))
    )
    (net (code "132") (name "unconnected-(U2-51-Pad52)") (class "Default")
      (node (ref "U2") (pin "52") (pinfunction "51_52") (pintype "passive"))
    )
    (net (code "133") (name "unconnected-(U2-52-Pad53)") (class "Default")
      (node (ref "U2") (pin "53") (pinfunction "52_53") (pintype "passive"))
    )
    (net (code "134") (name "unconnected-(U2-53-Pad54)") (class "Default")
      (node (ref "U2") (pin "54") (pinfunction "53_54") (pintype "passive"))
    )
    (net (code "135") (name "unconnected-(U2-54-Pad55)") (class "Default")
      (node (ref "U2") (pin "55") (pinfunction "54_55") (pintype "passive"))
    )
    (net (code "136") (name "unconnected-(U2-A1-Pad8)") (class "Default")
      (node (ref "U2") (pin "8") (pinfunction "A1_8") (pintype "passive"))
    )
    (net (code "137") (name "unconnected-(U2-A2-Pad9)") (class "Default")
      (node (ref "U2") (pin "9") (pinfunction "A2_9") (pintype "passive"))
    )
    (net (code "138") (name "unconnected-(U2-A3-Pad10)") (class "Default")
      (node (ref "U2") (pin "10") (pinfunction "A3_10") (pintype "passive"))
    )
    (net (code "139") (name "unconnected-(U2-A4-Pad11)") (class "Default")
      (node (ref "U2") (pin "11") (pinfunction "A4_11") (pintype "passive"))
    )
    (net (code "140") (name "unconnected-(U2-A5-Pad12)") (class "Default")
      (node (ref "U2") (pin "12") (pinfunction "A5_12") (pintype "passive"))
    )
    (net (code "141") (name "unconnected-(U2-A6-Pad13)") (class "Default")
      (node (ref "U2") (pin "13") (pinfunction "A6_13") (pintype "passive"))
    )
    (net (code "142") (name "unconnected-(U2-A7-Pad14)") (class "Default")
      (node (ref "U2") (pin "14") (pinfunction "A7_14") (pintype "passive"))
    )
    (net (code "143") (name "unconnected-(U2-A8-Pad15)") (class "Default")
      (node (ref "U2") (pin "15") (pinfunction "A8_15") (pintype "passive"))
    )
    (net (code "144") (name "unconnected-(U2-A9-Pad16)") (class "Default")
      (node (ref "U2") (pin "16") (pinfunction "A9_16") (pintype "passive"))
    )
    (net (code "145") (name "unconnected-(U2-A10-Pad17)") (class "Default")
      (node (ref "U2") (pin "17") (pinfunction "A10_17") (pintype "passive"))
    )
    (net (code "146") (name "unconnected-(U2-A11-Pad18)") (class "Default")
      (node (ref "U2") (pin "18") (pinfunction "A11_18") (pintype "passive"))
    )
    (net (code "147") (name "unconnected-(U2-A12-Pad19)") (class "Default")
      (node (ref "U2") (pin "19") (pinfunction "A12_19") (pintype "passive"))
    )
    (net (code "148") (name "unconnected-(U2-A13-Pad20)") (class "Default")
      (node (ref "U2") (pin "20") (pinfunction "A13_20") (pintype "passive"))
    )
    (net (code "149") (name "unconnected-(U2-A14-Pad21)") (class "Default")
      (node (ref "U2") (pin "21") (pinfunction "A14_21") (pintype "passive"))
    )
    (net (code "150") (name "unconnected-(U2-A15-Pad22)") (class "Default")
      (node (ref "U2") (pin "22") (pinfunction "A15_22") (pintype "passive"))
    )
    (net (code "151") (name "unconnected-(U2-AREF-Pad80)") (class "Default")
      (node (ref "U2") (pin "80") (pinfunction "AREF_80") (pintype "passive"))
    )
    (net (code "152") (name "unconnected-(U2-GND-Pad56)") (class "Default")
      (node (ref "U2") (pin "56") (pinfunction "GND_56") (pintype "passive"))
    )
    (net (code "153") (name "unconnected-(U2-GND-Pad79)") (class "Default")
      (node (ref "U2") (pin "79") (pinfunction "GND_79") (pintype "passive"))
    )
    (net (code "154") (name "unconnected-(U2-RESET-Pad1)") (class "Default")
      (node (ref "U2") (pin "1") (pinfunction "RESET_1") (pintype "passive"))
    )
    (net (code "155") (name "unconnected-(U2-RX0-Pad65)") (class "Default")
      (node (ref "U2") (pin "65") (pinfunction "RX0_65") (pintype "passive"))
    )
    (net (code "156") (name "unconnected-(U2-RX1-Pad59)") (class "Default")
      (node (ref "U2") (pin "59") (pinfunction "RX1_59") (pintype "passive"))
    )
    (net (code "157") (name "unconnected-(U2-RX3-Pad63)") (class "Default")
      (node (ref "U2") (pin "63") (pinfunction "RX3_63") (pintype "passive"))
    )
    (net (code "158") (name "unconnected-(U2-SCL-Pad57)") (class "Default")
      (node (ref "U2") (pin "57") (pinfunction "SCL_57") (pintype "passive"))
    )
    (net (code "159") (name "unconnected-(U2-SDA-Pad58)") (class "Default")
      (node (ref "U2") (pin "58") (pinfunction "SDA_58") (pintype "passive"))
    )
    (net (code "160") (name "unconnected-(U2-TX0-Pad66)") (class "Default")
      (node (ref "U2") (pin "66") (pinfunction "TX0_66") (pintype "passive"))
    )
    (net (code "161") (name "unconnected-(U2-TX1-Pad60)") (class "Default")
      (node (ref "U2") (pin "60") (pinfunction "TX1_60") (pintype "passive"))
    )
    (net (code "162") (name "unconnected-(U2-TX3-Pad64)") (class "Default")
      (node (ref "U2") (pin "64") (pinfunction "TX3_64") (pintype "passive"))
    )
    (net (code "163") (name "unconnected-(U2-Vin-Pad6)") (class "Default")
      (node (ref "U2") (pin "6") (pinfunction "Vin_6") (pintype "passive"))
    )
  )
)
